# schematic.net
KiCad netlist of a schematic drawn in EAGLE
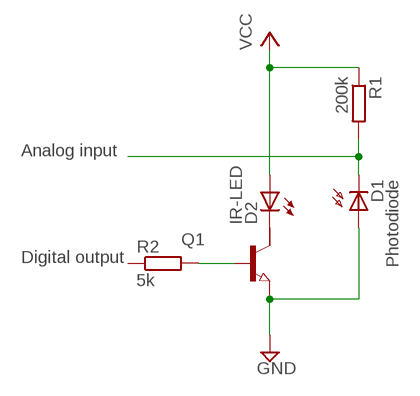
[diagram p0: schematic, sheet 1]

(export (version "E")
  (design (tool "Eeschema 10.0.6"))
  (components
    (comp (ref "D1")
      (value "Photodiode")
      (footprint "eagle-import:BP104")
      (fields (field (name "MF") "VISHAY/TELEFUNKEN") (field (name "MPN") "BP104"))
      (libsource (lib "eagle-import") (part "BP104"))
    )
    (comp (ref "D2")
      (value "IR-LED")
      (footprint "eagle-import:SFH482")
      (libsource (lib "eagle-import") (part "SFH482"))
    )
    (comp (ref "Q1")
      (value "NPN-TRANSISTIOR-2COLSOT89")
      (footprint "eagle-import:SOT89")
      (libsource (lib "eagle-import") (part "NPN-TRANSISTIOR-2COLSOT89"))
    )
    (comp (ref "R1")
      (value "200k")
      (footprint "eagle-import:0204_7")
      (libsource (lib "eagle-import") (part "R-EU_0204/7"))
    )
    (comp (ref "R2")
      (value "5k")
      (footprint "eagle-import:0204_7")
      (libsource (lib "eagle-import") (part "R-EU_0204/7"))
    )
  )
  (nets
    (net (code "1") (name "GND") (class "Default")
      (node (ref "D1") (pin "A") (pinfunction "A_A") (pintype "passive"))
      (node (ref "Q1") (pin "3") (pinfunction "E_3") (pintype "passive"))
    )
    (net (code "2") (name "Net-(D1-C)") (class "Default")
      (node (ref "D1") (pin "K") (pinfunction "C_K") (pintype "passive"))
      (node (ref "R1") (pin "2") (pinfunction "2_2") (pintype "passive"))
    )
    (net (code "3") (name "Net-(D2-C)") (class "Default")
      (node (ref "D2") (pin "K") (pinfunction "C_K") (pintype "passive"))
      (node (ref "Q1") (pin "2") (pinfunction "C_2") (pintype "passive"))
    )
    (net (code "4") (name "Net-(Q1-B)") (class "Default")
      (node (ref "Q1") (pin "1") (pinfunction "B_1") (pintype "passive"))
      (node (ref "R2") (pin "2") (pinfunction "2_2") (pintype "passive"))
    )
    (net (code "5") (name "VCC") (class "Default")
      (node (ref "D2") (pin "A") (pinfunction "A_A") (pintype "passive"))
      (node (ref "R1") (pin "1") (pinfunction "1_1") (pintype "passive"))
    )
    (net (code "6") (name "unconnected-(Q1-C{slash}-Pad2@1)") (class "Default")
      (node (ref "Q1") (pin "2@1") (pinfunction "C/_2@1") (pintype "passive"))
    )
    (net (code "7") (name "unconnected-(R2-Pad1)") (class "Default")
      (node (ref "R2") (pin "1") (pinfunction "1_1") (pintype "passive"))
    )
  )
)
